# DRV8432.net
KiCad netlist of a schematic drawn in Altium Designer
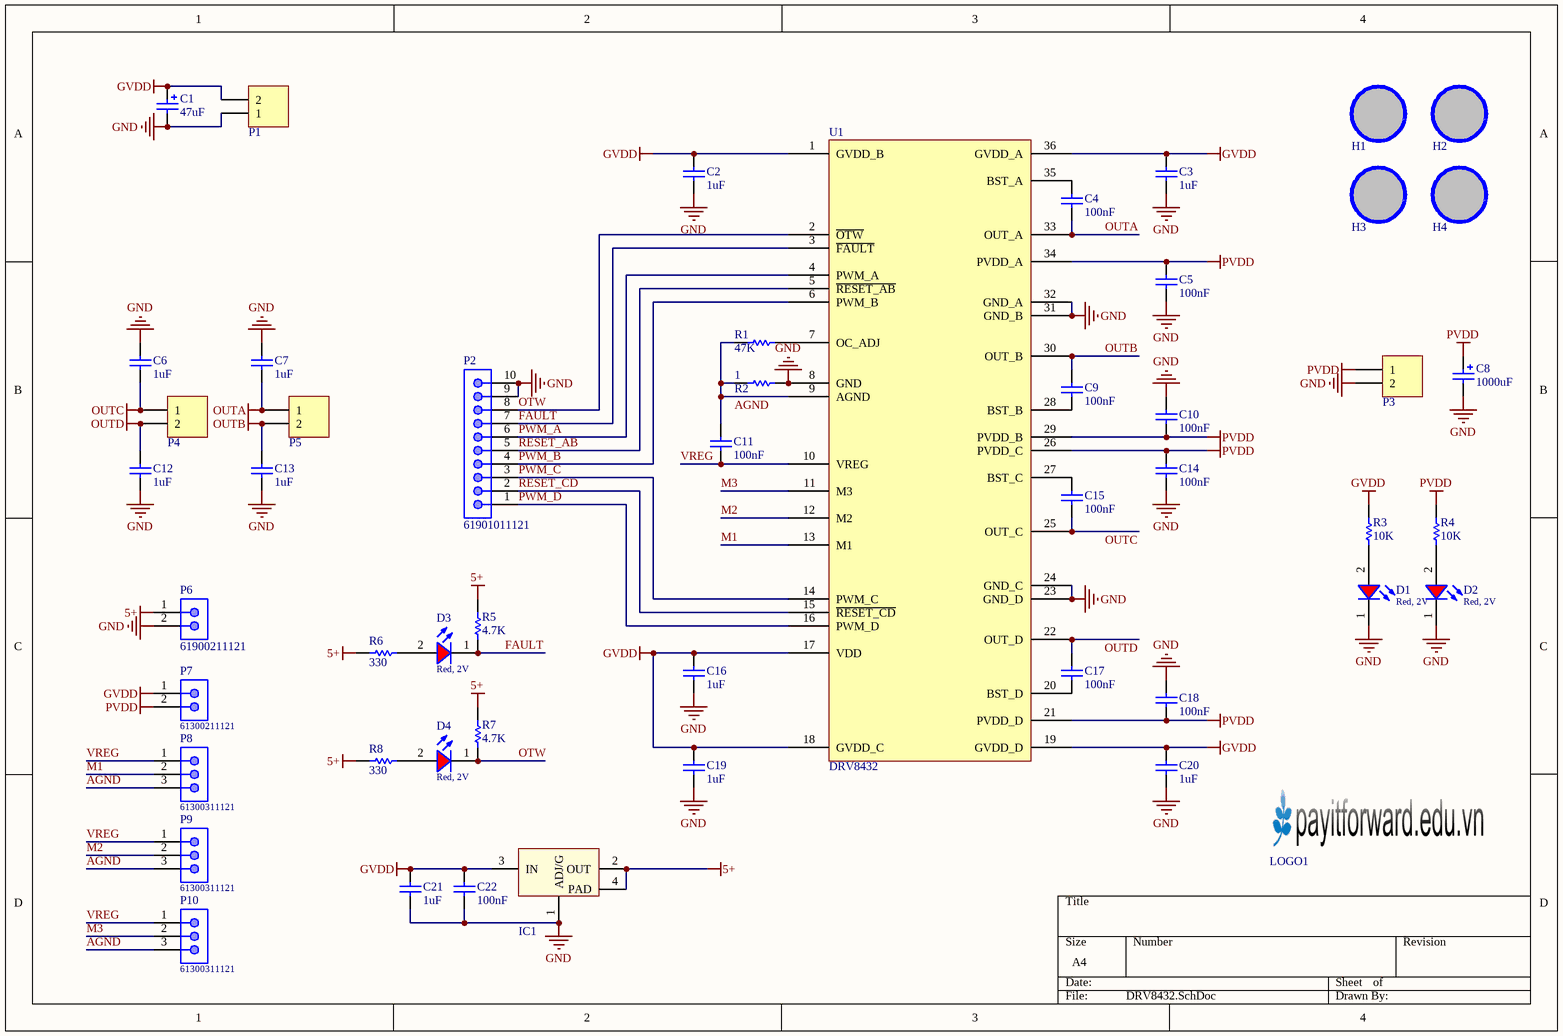
[diagram p0: DRV8432.SchDoc]

(export (version "E")
  (design (tool "Eeschema 10.0.6"))
  (components
    (comp (ref "C1")
      (value "47uF")
      (footprint "CAP ALU SIZE D")
      (description "Polarized Capacitor (Radial)")
      (fields (field (name "Comment") "Cap Pol SMD"))
      (libsource (lib "PIF_Library") (part "Cap Pol SMD"))
    )
    (comp (ref "C2")
      (value "1uF")
      (footprint "CAP-SM-0603")
      (description "Capacitor")
      (fields (field (name "Comment") "Cap Non-Pol SMD"))
      (libsource (lib "PIF_Library") (part "Cap Non-Pol SMD"))
    )
    (comp (ref "C3")
      (value "1uF")
      (footprint "CAP-SM-0603")
      (description "Capacitor")
      (fields (field (name "Comment") "Cap Non-Pol SMD"))
      (libsource (lib "PIF_Library") (part "Cap Non-Pol SMD"))
    )
    (comp (ref "C4")
      (value "100nF")
      (footprint "CAP-SM-0603")
      (description "Capacitor")
      (fields (field (name "Comment") "Cap Non-Pol SMD"))
      (libsource (lib "PIF_Library") (part "Cap Non-Pol SMD"))
    )
    (comp (ref "C5")
      (value "100nF")
      (footprint "CAP-SM-0603")
      (description "Capacitor")
      (fields (field (name "Comment") "Cap Non-Pol SMD"))
      (libsource (lib "PIF_Library") (part "Cap Non-Pol SMD"))
    )
    (comp (ref "C6")
      (value "1uF")
      (footprint "CAP-SM-0805")
      (description "Capacitor")
      (fields (field (name "Comment") "Cap Non-Pol SMD"))
      (libsource (lib "PIF_Library") (part "Cap Non-Pol SMD"))
    )
    (comp (ref "C7")
      (value "1uF")
      (footprint "CAP-SM-0805")
      (description "Capacitor")
      (fields (field (name "Comment") "Cap Non-Pol SMD"))
      (libsource (lib "PIF_Library") (part "Cap Non-Pol SMD"))
    )
    (comp (ref "C8")
      (value "1000uF")
      (footprint "CP2/5")
      (description "Polarized Capacitor (Radial)")
      (fields (field (name "Comment") "Cap Pol"))
      (libsource (lib "PIF_Library") (part "Cap Pol"))
    )
    (comp (ref "C9")
      (value "100nF")
      (footprint "CAP-SM-0603")
      (description "Capacitor")
      (fields (field (name "Comment") "Cap Non-Pol SMD"))
      (libsource (lib "PIF_Library") (part "Cap Non-Pol SMD"))
    )
    (comp (ref "C10")
      (value "100nF")
      (footprint "CAP-SM-0603")
      (description "Capacitor")
      (fields (field (name "Comment") "Cap Non-Pol SMD"))
      (libsource (lib "PIF_Library") (part "Cap Non-Pol SMD"))
    )
    (comp (ref "C11")
      (value "100nF")
      (footprint "CAP-SM-0603")
      (description "Capacitor")
      (fields (field (name "Comment") "Cap Non-Pol SMD"))
      (libsource (lib "PIF_Library") (part "Cap Non-Pol SMD"))
    )
    (comp (ref "C12")
      (value "1uF")
      (footprint "CAP-SM-0805")
      (description "Capacitor")
      (fields (field (name "Comment") "Cap Non-Pol SMD"))
      (libsource (lib "PIF_Library") (part "Cap Non-Pol SMD"))
    )
    (comp (ref "C13")
      (value "1uF")
      (footprint "CAP-SM-0805")
      (description "Capacitor")
      (fields (field (name "Comment") "Cap Non-Pol SMD"))
      (libsource (lib "PIF_Library") (part "Cap Non-Pol SMD"))
    )
    (comp (ref "C14")
      (value "100nF")
      (footprint "CAP-SM-0603")
      (description "Capacitor")
      (fields (field (name "Comment") "Cap Non-Pol SMD"))
      (libsource (lib "PIF_Library") (part "Cap Non-Pol SMD"))
    )
    (comp (ref "C15")
      (value "100nF")
      (footprint "CAP-SM-0603")
      (description "Capacitor")
      (fields (field (name "Comment") "Cap Non-Pol SMD"))
      (libsource (lib "PIF_Library") (part "Cap Non-Pol SMD"))
    )
    (comp (ref "C16")
      (value "1uF")
      (footprint "CAP-SM-0603")
      (description "Capacitor")
      (fields (field (name "Comment") "Cap Non-Pol SMD"))
      (libsource (lib "PIF_Library") (part "Cap Non-Pol SMD"))
    )
    (comp (ref "C17")
      (value "100nF")
      (footprint "CAP-SM-0603")
      (description "Capacitor")
      (fields (field (name "Comment") "Cap Non-Pol SMD"))
      (libsource (lib "PIF_Library") (part "Cap Non-Pol SMD"))
    )
    (comp (ref "C18")
      (value "100nF")
      (footprint "CAP-SM-0603")
      (description "Capacitor")
      (fields (field (name "Comment") "Cap Non-Pol SMD"))
      (libsource (lib "PIF_Library") (part "Cap Non-Pol SMD"))
    )
    (comp (ref "C19")
      (value "1uF")
      (footprint "CAP-SM-0603")
      (description "Capacitor")
      (fields (field (name "Comment") "Cap Non-Pol SMD"))
      (libsource (lib "PIF_Library") (part "Cap Non-Pol SMD"))
    )
    (comp (ref "C20")
      (value "1uF")
      (footprint "CAP-SM-0603")
      (description "Capacitor")
      (fields (field (name "Comment") "Cap Non-Pol SMD"))
      (libsource (lib "PIF_Library") (part "Cap Non-Pol SMD"))
    )
    (comp (ref "C21")
      (value "1uF")
      (footprint "CAP-SM-0603")
      (description "Capacitor")
      (fields (field (name "Comment") "Cap Non-Pol SMD"))
      (libsource (lib "PIF_Library") (part "Cap Non-Pol SMD"))
    )
    (comp (ref "C22")
      (value "100nF")
      (footprint "CAP-SM-0603")
      (description "Capacitor")
      (fields (field (name "Comment") "Cap Non-Pol SMD"))
      (libsource (lib "PIF_Library") (part "Cap Non-Pol SMD"))
    )
    (comp (ref "D1")
      (value "Red, 2V")
      (footprint "WL-SMCW_0603_H=0.7mm")
      (description "WL-SMCW SMT Mono-color Chip LED Waterclear, size 0603, Red, 2V, 140deg")
      (fields (field (name "PART NUMBER") "150060RS75000") (field (name "PUBLISHER") "Wurth Elektronik"))
      (libsource (lib "Altium_WL-SMCW (rev20a)") (part "150060RS75000"))
    )
    (comp (ref "D2")
      (value "Red, 2V")
      (footprint "WL-SMCW_0603_H=0.7mm")
      (description "WL-SMCW SMT Mono-color Chip LED Waterclear, size 0603, Red, 2V, 140deg")
      (fields (field (name "PART NUMBER") "150060RS75000") (field (name "PUBLISHER") "Wurth Elektronik"))
      (libsource (lib "Altium_WL-SMCW (rev20a)") (part "150060RS75000"))
    )
    (comp (ref "D3")
      (value "Red, 2V")
      (footprint "WL-SMCW_0603_H=0.7mm")
      (description "WL-SMCW SMT Mono-color Chip LED Waterclear, size 0603, Red, 2V, 140deg")
      (fields (field (name "PART NUMBER") "150060RS75000") (field (name "PUBLISHER") "Wurth Elektronik"))
      (libsource (lib "Altium_WL-SMCW (rev20a)") (part "150060RS75000"))
    )
    (comp (ref "D4")
      (value "Red, 2V")
      (footprint "WL-SMCW_0603_H=0.7mm")
      (description "WL-SMCW SMT Mono-color Chip LED Waterclear, size 0603, Red, 2V, 140deg")
      (fields (field (name "PART NUMBER") "150060RS75000") (field (name "PUBLISHER") "Wurth Elektronik"))
      (libsource (lib "Altium_WL-SMCW (rev20a)") (part "150060RS75000"))
    )
    (comp (ref "H1")
      (value "Hole")
      (footprint "LO KHOAN 3MM")
      (description "Hole 3mm")
      (libsource (lib "PIF_Library") (part "Hole"))
    )
    (comp (ref "H2")
      (value "Hole")
      (footprint "LO KHOAN 3MM")
      (description "Hole 3mm")
      (libsource (lib "PIF_Library") (part "Hole"))
    )
    (comp (ref "H3")
      (value "Hole")
      (footprint "LO KHOAN 3MM")
      (description "Hole 3mm")
      (libsource (lib "PIF_Library") (part "Hole"))
    )
    (comp (ref "H4")
      (value "Hole")
      (footprint "LO KHOAN 3MM")
      (description "Hole 3mm")
      (libsource (lib "PIF_Library") (part "Hole"))
    )
    (comp (ref "IC1")
      (value "LM1117")
      (footprint "SOT223-4N")
      (description "Available in 1.8V, 2.5V, 2.85V, 3.3V, 5V, and  Adjustable Versions")
      (libsource (lib "PIF_Library") (part "LM1117"))
    )
    (comp (ref "LOGO1")
      (value "LOGO PIF")
      (footprint "PIF LOGO SMALL TOP")
      (libsource (lib "PIF_Library") (part "LOGO PIF"))
    )
    (comp (ref "P1")
      (value "Domino 2")
      (footprint "DOMINO 2- 5mm")
      (description "Domino, 2-Pin")
      (fields (field (name "PUBLISHER") "Altium Limited"))
      (libsource (lib "") (part "Domino 2_1"))
    )
    (comp (ref "P2")
      (value "61901011121")
      (footprint "61901011121")
      (description "WR-WTB THT Male Vertical Locking Header, pitch 2.54mm, 10p")
      (fields (field (name "PUBLISHER") "Wurth Elektronik"))
      (libsource (lib "653008114822_Altium_WR-WTB_rev20a") (part "61901011121"))
    )
    (comp (ref "P3")
      (value "Domino 2")
      (footprint "DOMINO 2- 5mm")
      (description "Domino, 2-Pin")
      (fields (field (name "PUBLISHER") "Altium Limited"))
      (libsource (lib "PIF_Library") (part "Domino 2"))
    )
    (comp (ref "P4")
      (value "Domino 2")
      (footprint "DOMINO 2- 5mm")
      (description "Domino, 2-Pin")
      (fields (field (name "PUBLISHER") "Altium Limited"))
      (libsource (lib "PIF_Library") (part "Domino 2"))
    )
    (comp (ref "P5")
      (value "Domino 2")
      (footprint "DOMINO 2- 5mm")
      (description "Domino, 2-Pin")
      (fields (field (name "PUBLISHER") "Altium Limited"))
      (libsource (lib "PIF_Library") (part "Domino 2"))
    )
    (comp (ref "P6")
      (value "61900211121")
      (footprint "61900211121")
      (description "WR-WTB THT Male Vertical Locking Header, pitch 2.54mm, 2p")
      (fields (field (name "PUBLISHER") "Wurth Elektronik"))
      (libsource (lib "653008114822_Altium_WR-WTB_rev20a") (part "61900211121"))
    )
    (comp (ref "P7")
      (value "61300211121")
      (footprint "61300211121")
      (description "WR-PHD Pin Header, THT, pitch 2.54mm, Single Row, Vertical, 2p")
      (fields (field (name "MANUFACTURER") "Wurth Elektronik"))
      (libsource (lib "Altium_WR-PHD (rev20a)") (part "61300211121"))
    )
    (comp (ref "P8")
      (value "61300311121")
      (footprint "61300311121")
      (description "WR-PHD Pin Header, THT, pitch 2.54mm, Single Row, Vertical, 3p")
      (fields (field (name "MANUFACTURER") "Wurth Elektronik"))
      (libsource (lib "Altium_WR-PHD (rev20a)") (part "61300311121"))
    )
    (comp (ref "P9")
      (value "61300311121")
      (footprint "61300311121")
      (description "WR-PHD Pin Header, THT, pitch 2.54mm, Single Row, Vertical, 3p")
      (fields (field (name "MANUFACTURER") "Wurth Elektronik"))
      (libsource (lib "Altium_WR-PHD (rev20a)") (part "61300311121"))
    )
    (comp (ref "P10")
      (value "61300311121")
      (footprint "61300311121")
      (description "WR-PHD Pin Header, THT, pitch 2.54mm, Single Row, Vertical, 3p")
      (fields (field (name "MANUFACTURER") "Wurth Elektronik"))
      (libsource (lib "Altium_WR-PHD (rev20a)") (part "61300311121"))
    )
    (comp (ref "R1")
      (value "47K")
      (footprint "RES-SM-0603")
      (description "Resistor")
      (fields (field (name "Comment") "RESISTOR SMD"))
      (libsource (lib "PIF_Library") (part "RESISTOR SMD"))
    )
    (comp (ref "R2")
      (value "1")
      (footprint "RES-SM-0603")
      (description "Resistor")
      (fields (field (name "Comment") "RESISTOR SMD"))
      (libsource (lib "PIF_Library") (part "RESISTOR SMD"))
    )
    (comp (ref "R3")
      (value "10K")
      (footprint "RES-SM-0603")
      (description "Resistor")
      (fields (field (name "Comment") "RESISTOR SMD"))
      (libsource (lib "PIF_Library") (part "RESISTOR SMD"))
    )
    (comp (ref "R4")
      (value "10K")
      (footprint "RES-SM-0603")
      (description "Resistor")
      (fields (field (name "Comment") "RESISTOR SMD"))
      (libsource (lib "PIF_Library") (part "RESISTOR SMD"))
    )
    (comp (ref "R5")
      (value "4.7K")
      (footprint "RES-SM-0603")
      (description "Resistor")
      (fields (field (name "Comment") "RESISTOR SMD"))
      (libsource (lib "PIF_Library") (part "RESISTOR SMD"))
    )
    (comp (ref "R6")
      (value "330")
      (footprint "RES-SM-0603")
      (description "Resistor")
      (fields (field (name "Comment") "RESISTOR SMD"))
      (libsource (lib "PIF_Library") (part "RESISTOR SMD"))
    )
    (comp (ref "R7")
      (value "4.7K")
      (footprint "RES-SM-0603")
      (description "Resistor")
      (fields (field (name "Comment") "RESISTOR SMD"))
      (libsource (lib "PIF_Library") (part "RESISTOR SMD"))
    )
    (comp (ref "R8")
      (value "330")
      (footprint "RES-SM-0603")
      (description "Resistor")
      (fields (field (name "Comment") "RESISTOR SMD"))
      (libsource (lib "PIF_Library") (part "RESISTOR SMD"))
    )
    (comp (ref "U1")
      (value "DRV8432")
      (footprint "SOP65P1420X360-36N")
      (libsource (lib "MiclsLib") (part "DRV8432"))
    )
  )
  (nets
    (net (code "1") (name "/AGND") (class "Default")
      (node (ref "C11") (pin "2") (pinfunction "2_2") (pintype "passive"))
      (node (ref "P10") (pin "3") (pinfunction "3_3") (pintype "passive"))
      (node (ref "P8") (pin "3") (pinfunction "3_3") (pintype "passive"))
      (node (ref "P9") (pin "3") (pinfunction "3_3") (pintype "passive"))
      (node (ref "R1") (pin "1") (pinfunction "1_1") (pintype "passive"))
      (node (ref "R2") (pin "1") (pinfunction "1_1") (pintype "passive"))
      (node (ref "U1") (pin "9") (pinfunction "AGND_9") (pintype "passive"))
    )
    (net (code "2") (name "/FAULT") (class "Default")
      (node (ref "D3") (pin "1") (pinfunction "K_1") (pintype "passive"))
      (node (ref "P2") (pin "7") (pinfunction "7_7") (pintype "passive"))
      (node (ref "R5") (pin "1") (pinfunction "1_1") (pintype "passive"))
      (node (ref "U1") (pin "3") (pinfunction "~{FAULT}_3") (pintype "passive"))
    )
    (net (code "3") (name "/M1") (class "Default")
      (node (ref "P8") (pin "2") (pinfunction "2_2") (pintype "passive"))
      (node (ref "U1") (pin "13") (pinfunction "M1_13") (pintype "passive"))
    )
    (net (code "4") (name "/M2") (class "Default")
      (node (ref "P9") (pin "2") (pinfunction "2_2") (pintype "passive"))
      (node (ref "U1") (pin "12") (pinfunction "M2_12") (pintype "passive"))
    )
    (net (code "5") (name "/M3") (class "Default")
      (node (ref "P10") (pin "2") (pinfunction "2_2") (pintype "passive"))
      (node (ref "U1") (pin "11") (pinfunction "M3_11") (pintype "passive"))
    )
    (net (code "6") (name "/OTW") (class "Default")
      (node (ref "D4") (pin "1") (pinfunction "K_1") (pintype "passive"))
      (node (ref "P2") (pin "8") (pinfunction "8_8") (pintype "passive"))
      (node (ref "R7") (pin "1") (pinfunction "1_1") (pintype "passive"))
      (node (ref "U1") (pin "2") (pinfunction "~{OTW}_2") (pintype "passive"))
    )
    (net (code "7") (name "/PWM_A") (class "Default")
      (node (ref "P2") (pin "6") (pinfunction "6_6") (pintype "passive"))
      (node (ref "U1") (pin "4") (pinfunction "PWM_A_4") (pintype "passive"))
    )
    (net (code "8") (name "/PWM_B") (class "Default")
      (node (ref "P2") (pin "4") (pinfunction "4_4") (pintype "passive"))
      (node (ref "U1") (pin "6") (pinfunction "PWM_B_6") (pintype "passive"))
    )
    (net (code "9") (name "/PWM_C") (class "Default")
      (node (ref "P2") (pin "3") (pinfunction "3_3") (pintype "passive"))
      (node (ref "U1") (pin "14") (pinfunction "PWM_C_14") (pintype "passive"))
    )
    (net (code "10") (name "/PWM_D") (class "Default")
      (node (ref "P2") (pin "1") (pinfunction "1_1") (pintype "passive"))
      (node (ref "U1") (pin "16") (pinfunction "PWM_D_16") (pintype "passive"))
    )
    (net (code "11") (name "/RESET_AB") (class "Default")
      (node (ref "P2") (pin "5") (pinfunction "5_5") (pintype "passive"))
      (node (ref "U1") (pin "5") (pinfunction "~{RESET_AB}_5") (pintype "passive"))
    )
    (net (code "12") (name "/RESET_CD") (class "Default")
      (node (ref "P2") (pin "2") (pinfunction "2_2") (pintype "passive"))
      (node (ref "U1") (pin "15") (pinfunction "~{RESET_CD}_15") (pintype "passive"))
    )
    (net (code "13") (name "/VREG") (class "Default")
      (node (ref "C11") (pin "1") (pinfunction "1_1") (pintype "passive"))
      (node (ref "P10") (pin "1") (pinfunction "1_1") (pintype "passive"))
      (node (ref "P8") (pin "1") (pinfunction "1_1") (pintype "passive"))
      (node (ref "P9") (pin "1") (pinfunction "1_1") (pintype "passive"))
      (node (ref "U1") (pin "10") (pinfunction "VREG_10") (pintype "passive"))
    )
    (net (code "14") (name "5+") (class "Default")
      (node (ref "IC1") (pin "2") (pinfunction "OUT_2") (pintype "passive"))
      (node (ref "IC1") (pin "4") (pinfunction "PAD_4") (pintype "passive"))
      (node (ref "P6") (pin "1") (pinfunction "1_1") (pintype "passive"))
      (node (ref "R5") (pin "2") (pinfunction "2_2") (pintype "passive"))
      (node (ref "R6") (pin "2") (pinfunction "2_2") (pintype "passive"))
      (node (ref "R7") (pin "2") (pinfunction "2_2") (pintype "passive"))
      (node (ref "R8") (pin "2") (pinfunction "2_2") (pintype "passive"))
    )
    (net (code "15") (name "GND") (class "Default")
      (node (ref "C1") (pin "2") (pinfunction "2_2") (pintype "passive"))
      (node (ref "C10") (pin "2") (pinfunction "2_2") (pintype "passive"))
      (node (ref "C12") (pin "1") (pinfunction "1_1") (pintype "passive"))
      (node (ref "C13") (pin "1") (pinfunction "1_1") (pintype "passive"))
      (node (ref "C14") (pin "1") (pinfunction "1_1") (pintype "passive"))
      (node (ref "C16") (pin "1") (pinfunction "1_1") (pintype "passive"))
      (node (ref "C18") (pin "2") (pinfunction "2_2") (pintype "passive"))
      (node (ref "C19") (pin "1") (pinfunction "1_1") (pintype "passive"))
      (node (ref "C2") (pin "1") (pinfunction "1_1") (pintype "passive"))
      (node (ref "C20") (pin "1") (pinfunction "1_1") (pintype "passive"))
      (node (ref "C21") (pin "1") (pinfunction "1_1") (pintype "passive"))
      (node (ref "C22") (pin "1") (pinfunction "1_1") (pintype "passive"))
      (node (ref "C3") (pin "1") (pinfunction "1_1") (pintype "passive"))
      (node (ref "C5") (pin "1") (pinfunction "1_1") (pintype "passive"))
      (node (ref "C6") (pin "2") (pinfunction "2_2") (pintype "passive"))
      (node (ref "C7") (pin "2") (pinfunction "2_2") (pintype "passive"))
      (node (ref "C8") (pin "2") (pinfunction "2_2") (pintype "passive"))
      (node (ref "D1") (pin "1") (pinfunction "K_1") (pintype "passive"))
      (node (ref "D2") (pin "1") (pinfunction "K_1") (pintype "passive"))
      (node (ref "IC1") (pin "1") (pinfunction "ADJ/G_1") (pintype "passive"))
      (node (ref "P1") (pin "1") (pinfunction "1_1") (pintype "passive"))
      (node (ref "P2") (pin "10") (pinfunction "10_10") (pintype "passive"))
      (node (ref "P2") (pin "9") (pinfunction "9_9") (pintype "passive"))
      (node (ref "P3") (pin "2") (pinfunction "2_2") (pintype "passive"))
      (node (ref "P6") (pin "2") (pinfunction "2_2") (pintype "passive"))
      (node (ref "R2") (pin "2") (pinfunction "2_2") (pintype "passive"))
      (node (ref "U1") (pin "23") (pinfunction "GND_D_23") (pintype "passive"))
      (node (ref "U1") (pin "24") (pinfunction "GND_C_24") (pintype "passive"))
      (node (ref "U1") (pin "31") (pinfunction "GND_B_31") (pintype "passive"))
      (node (ref "U1") (pin "32") (pinfunction "GND_A_32") (pintype "passive"))
      (node (ref "U1") (pin "8") (pinfunction "GND_8") (pintype "passive"))
    )
    (net (code "16") (name "GVDD") (class "Default")
      (node (ref "C1") (pin "1") (pinfunction "1_1") (pintype "passive"))
      (node (ref "C16") (pin "2") (pinfunction "2_2") (pintype "passive"))
      (node (ref "C19") (pin "2") (pinfunction "2_2") (pintype "passive"))
      (node (ref "C2") (pin "2") (pinfunction "2_2") (pintype "passive"))
      (node (ref "C20") (pin "2") (pinfunction "2_2") (pintype "passive"))
      (node (ref "C21") (pin "2") (pinfunction "2_2") (pintype "passive"))
      (node (ref "C22") (pin "2") (pinfunction "2_2") (pintype "passive"))
      (node (ref "C3") (pin "2") (pinfunction "2_2") (pintype "passive"))
      (node (ref "IC1") (pin "3") (pinfunction "IN_3") (pintype "passive"))
      (node (ref "P1") (pin "2") (pinfunction "2_2") (pintype "passive"))
      (node (ref "P7") (pin "1") (pinfunction "1_1") (pintype "passive"))
      (node (ref "R3") (pin "1") (pinfunction "1_1") (pintype "passive"))
      (node (ref "U1") (pin "1") (pinfunction "GVDD_B_1") (pintype "passive"))
      (node (ref "U1") (pin "17") (pinfunction "VDD_17") (pintype "passive"))
      (node (ref "U1") (pin "18") (pinfunction "GVDD_C_18") (pintype "passive"))
      (node (ref "U1") (pin "19") (pinfunction "GVDD_D_19") (pintype "passive"))
      (node (ref "U1") (pin "36") (pinfunction "GVDD_A_36") (pintype "passive"))
    )
    (net (code "17") (name "Net-(D1-A)") (class "Default")
      (node (ref "D1") (pin "2") (pinfunction "A_2") (pintype "passive"))
      (node (ref "R3") (pin "2") (pinfunction "2_2") (pintype "passive"))
    )
    (net (code "18") (name "Net-(D2-A)") (class "Default")
      (node (ref "D2") (pin "2") (pinfunction "A_2") (pintype "passive"))
      (node (ref "R4") (pin "2") (pinfunction "2_2") (pintype "passive"))
    )
    (net (code "19") (name "Net-(D3-A)") (class "Default")
      (node (ref "D3") (pin "2") (pinfunction "A_2") (pintype "passive"))
      (node (ref "R6") (pin "1") (pinfunction "1_1") (pintype "passive"))
    )
    (net (code "20") (name "Net-(D4-A)") (class "Default")
      (node (ref "D4") (pin "2") (pinfunction "A_2") (pintype "passive"))
      (node (ref "R8") (pin "1") (pinfunction "1_1") (pintype "passive"))
    )
    (net (code "21") (name "Net-(U1-BST_A)") (class "Default")
      (node (ref "C4") (pin "2") (pinfunction "2_2") (pintype "passive"))
      (node (ref "U1") (pin "35") (pinfunction "BST_A_35") (pintype "passive"))
    )
    (net (code "22") (name "Net-(U1-BST_B)") (class "Default")
      (node (ref "C9") (pin "1") (pinfunction "1_1") (pintype "passive"))
      (node (ref "U1") (pin "28") (pinfunction "BST_B_28") (pintype "passive"))
    )
    (net (code "23") (name "Net-(U1-BST_C)") (class "Default")
      (node (ref "C15") (pin "2") (pinfunction "2_2") (pintype "passive"))
      (node (ref "U1") (pin "27") (pinfunction "BST_C_27") (pintype "passive"))
    )
    (net (code "24") (name "Net-(U1-BST_D)") (class "Default")
      (node (ref "C17") (pin "1") (pinfunction "1_1") (pintype "passive"))
      (node (ref "U1") (pin "20") (pinfunction "BST_D_20") (pintype "passive"))
    )
    (net (code "25") (name "Net-(U1-OC_ADJ)") (class "Default")
      (node (ref "R1") (pin "2") (pinfunction "2_2") (pintype "passive"))
      (node (ref "U1") (pin "7") (pinfunction "OC_ADJ_7") (pintype "passive"))
    )
    (net (code "26") (name "OUTA") (class "Default")
      (node (ref "C4") (pin "1") (pinfunction "1_1") (pintype "passive"))
      (node (ref "C7") (pin "1") (pinfunction "1_1") (pintype "passive"))
      (node (ref "P5") (pin "1") (pinfunction "1_1") (pintype "passive"))
      (node (ref "U1") (pin "33") (pinfunction "OUT_A_33") (pintype "passive"))
    )
    (net (code "27") (name "OUTB") (class "Default")
      (node (ref "C13") (pin "2") (pinfunction "2_2") (pintype "passive"))
      (node (ref "C9") (pin "2") (pinfunction "2_2") (pintype "passive"))
      (node (ref "P5") (pin "2") (pinfunction "2_2") (pintype "passive"))
      (node (ref "U1") (pin "30") (pinfunction "OUT_B_30") (pintype "passive"))
    )
    (net (code "28") (name "OUTC") (class "Default")
      (node (ref "C15") (pin "1") (pinfunction "1_1") (pintype "passive"))
      (node (ref "C6") (pin "1") (pinfunction "1_1") (pintype "passive"))
      (node (ref "P4") (pin "1") (pinfunction "1_1") (pintype "passive"))
      (node (ref "U1") (pin "25") (pinfunction "OUT_C_25") (pintype "passive"))
    )
    (net (code "29") (name "OUTD") (class "Default")
      (node (ref "C12") (pin "2") (pinfunction "2_2") (pintype "passive"))
      (node (ref "C17") (pin "2") (pinfunction "2_2") (pintype "passive"))
      (node (ref "P4") (pin "2") (pinfunction "2_2") (pintype "passive"))
      (node (ref "U1") (pin "22") (pinfunction "OUT_D_22") (pintype "passive"))
    )
    (net (code "30") (name "PVDD") (class "Default")
      (node (ref "C10") (pin "1") (pinfunction "1_1") (pintype "passive"))
      (node (ref "C14") (pin "2") (pinfunction "2_2") (pintype "passive"))
      (node (ref "C18") (pin "1") (pinfunction "1_1") (pintype "passive"))
      (node (ref "C5") (pin "2") (pinfunction "2_2") (pintype "passive"))
      (node (ref "C8") (pin "1") (pinfunction "1_1") (pintype "passive"))
      (node (ref "P3") (pin "1") (pinfunction "1_1") (pintype "passive"))
      (node (ref "P7") (pin "2") (pinfunction "2_2") (pintype "passive"))
      (node (ref "R4") (pin "1") (pinfunction "1_1") (pintype "passive"))
      (node (ref "U1") (pin "21") (pinfunction "PVDD_D_21") (pintype "passive"))
      (node (ref "U1") (pin "26") (pinfunction "PVDD_C_26") (pintype "passive"))
      (node (ref "U1") (pin "29") (pinfunction "PVDD_B_29") (pintype "passive"))
      (node (ref "U1") (pin "34") (pinfunction "PVDD_A_34") (pintype "passive"))
    )
    (net (code "31") (name "unconnected-(H1-Pad1)") (class "Default")
      (node (ref "H1") (pin "1") (pinfunction "1_1") (pintype "passive"))
    )
    (net (code "32") (name "unconnected-(H2-Pad1)") (class "Default")
      (node (ref "H2") (pin "1") (pinfunction "1_1") (pintype "passive"))
    )
    (net (code "33") (name "unconnected-(H3-Pad1)") (class "Default")
      (node (ref "H3") (pin "1") (pinfunction "1_1") (pintype "passive"))
    )
    (net (code "34") (name "unconnected-(H4-Pad1)") (class "Default")
      (node (ref "H4") (pin "1") (pinfunction "1_1") (pintype "passive"))
    )
  )
)
